# UART.net
KiCad netlist of a schematic drawn in Altium Designer
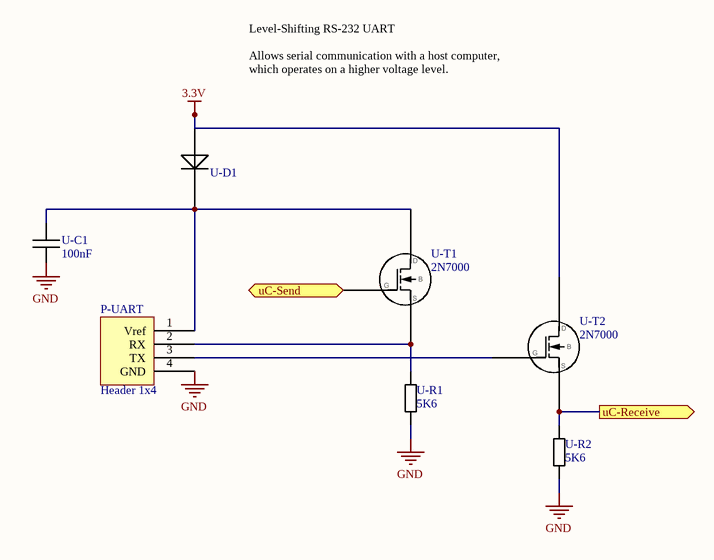
[diagram p0: UART.SchDoc]

(export (version "E")
  (design (tool "Eeschema 10.0.6"))
  (components
    (comp (ref "P-UART")
      (value "Header 1x4")
      (footprint "Header 1x4")
      (libsource (lib "Headers") (part "Header UART"))
    )
    (comp (ref "U-C1")
      (value "100nF")
      (footprint "C 0805 / 2012")
      (libsource (lib "Standard") (part "Capacitor"))
    )
    (comp (ref "U-D1") (value "Diode") (footprint "SC-90") (libsource (lib "Standard") (part "Diode")))
    (comp (ref "U-R1")
      (value "5K6")
      (footprint "R 0805 / 2012")
      (libsource (lib "Standard") (part "Resistor"))
    )
    (comp (ref "U-R2")
      (value "5K6")
      (footprint "R 0805 / 2012")
      (libsource (lib "Standard") (part "Resistor"))
    )
    (comp (ref "U-T1")
      (value "2N7000")
      (footprint "SOT-23-3")
      (description "N-FET")
      (libsource (lib "ICs") (part "2N7000"))
    )
    (comp (ref "U-T2")
      (value "2N7000")
      (footprint "SOT-23-3")
      (description "N-FET")
      (libsource (lib "ICs") (part "2N7000"))
    )
  )
  (nets
    (net (code "1") (name "/uC-Receive") (class "Default")
      (node (ref "U-R2") (pin "1") (pinfunction "1_1") (pintype "passive"))
      (node (ref "U-T2") (pin "2") (pinfunction "2_2") (pintype "passive"))
    )
    (net (code "2") (name "/uC-Send") (class "Default")
      (node (ref "U-T1") (pin "1") (pinfunction "1_1") (pintype "passive"))
    )
    (net (code "3") (name "3.3V") (class "Default")
      (node (ref "U-D1") (pin "2") (pinfunction "2_2") (pintype "passive"))
      (node (ref "U-T2") (pin "3") (pinfunction "3_3") (pintype "passive"))
    )
    (net (code "4") (name "GND") (class "Default")
      (node (ref "P-UART") (pin "4") (pinfunction "GND_4") (pintype "passive"))
      (node (ref "U-C1") (pin "2") (pinfunction "1_2") (pintype "passive"))
      (node (ref "U-R1") (pin "2") (pinfunction "2_2") (pintype "passive"))
      (node (ref "U-R2") (pin "2") (pinfunction "2_2") (pintype "passive"))
    )
    (net (code "5") (name "Net-(P-UART-RX)") (class "Default")
      (node (ref "P-UART") (pin "2") (pinfunction "RX_2") (pintype "passive"))
      (node (ref "U-R1") (pin "1") (pinfunction "1_1") (pintype "passive"))
      (node (ref "U-T1") (pin "2") (pinfunction "2_2") (pintype "passive"))
    )
    (net (code "6") (name "Net-(P-UART-TX)") (class "Default")
      (node (ref "P-UART") (pin "3") (pinfunction "TX_3") (pintype "passive"))
      (node (ref "U-T2") (pin "1") (pinfunction "1_1") (pintype "passive"))
    )
    (net (code "7") (name "Net-(P-UART-Vref)") (class "Default")
      (node (ref "P-UART") (pin "1") (pinfunction "Vref_1") (pintype "passive"))
      (node (ref "U-C1") (pin "1") (pinfunction "1_1") (pintype "passive"))
      (node (ref "U-D1") (pin "1") (pinfunction "1_1") (pintype "passive"))
      (node (ref "U-T1") (pin "3") (pinfunction "3_3") (pintype "passive"))
    )
  )
)
